# schematic.net
KiCad netlist of a schematic drawn in Altium Designer
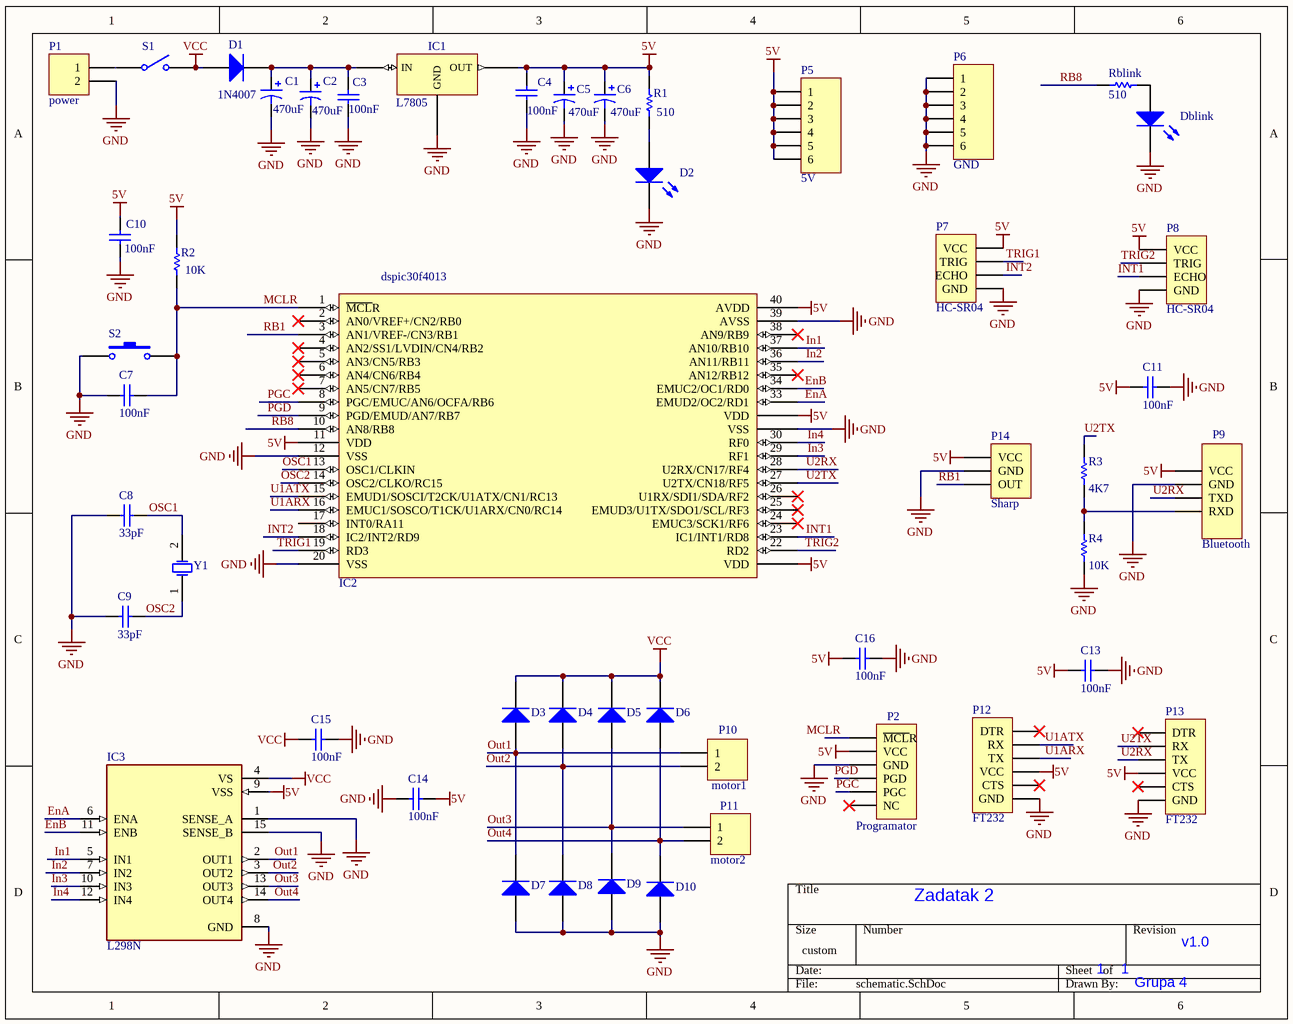
[diagram p0: schematic.SchDoc]

(export (version "E")
  (design (tool "Eeschema 10.0.6"))
  (components
    (comp (ref "C1")
      (value "470uF")
      (footprint "elektrolit")
      (description "Polarized Capacitor (Radial)")
      (fields (field (name "Comment") "Cap Pol1") (field (name "PUBLISHER") "Altium Limited"))
      (libsource (lib "Miscellaneous Devices") (part "Capacitor"))
    )
    (comp (ref "C2")
      (value "470uF")
      (footprint "elektrolit")
      (description "Polarized Capacitor (Radial)")
      (fields (field (name "Comment") "Cap Pol1") (field (name "PUBLISHER") "Altium Limited"))
      (libsource (lib "Miscellaneous Devices") (part "Capacitor"))
    )
    (comp (ref "C3")
      (value "100nF")
      (footprint "keramicki")
      (description "Capacitor")
      (fields (field (name "Comment") "Cap") (field (name "PUBLISHER") "Altium Limited"))
      (libsource (lib "Miscellaneous Devices") (part "Cap"))
    )
    (comp (ref "C4")
      (value "100nF")
      (footprint "keramicki")
      (description "Capacitor")
      (fields (field (name "Comment") "Cap") (field (name "PUBLISHER") "Altium Limited"))
      (libsource (lib "Miscellaneous Devices") (part "Cap"))
    )
    (comp (ref "C5")
      (value "470uF")
      (footprint "elektrolit")
      (description "Polarized Capacitor (Radial)")
      (fields (field (name "Comment") "Cap Pol1") (field (name "PUBLISHER") "Altium Limited"))
      (libsource (lib "Miscellaneous Devices") (part "Capacitor"))
    )
    (comp (ref "C6")
      (value "470uF")
      (footprint "elektrolit")
      (description "Polarized Capacitor (Radial)")
      (fields (field (name "Comment") "Cap Pol1") (field (name "PUBLISHER") "Altium Limited"))
      (libsource (lib "Miscellaneous Devices") (part "Capacitor"))
    )
    (comp (ref "C7")
      (value "100nF")
      (footprint "keramicki")
      (description "Capacitor")
      (fields (field (name "Comment") "Cap") (field (name "PUBLISHER") "Altium Limited"))
      (libsource (lib "Miscellaneous Devices") (part "Cap"))
    )
    (comp (ref "C8")
      (value "33pF")
      (footprint "keramicki")
      (description "Capacitor")
      (fields (field (name "Comment") "Cap") (field (name "PUBLISHER") "Altium Limited"))
      (libsource (lib "Miscellaneous Devices") (part "Cap"))
    )
    (comp (ref "C9")
      (value "33pF")
      (footprint "keramicki")
      (description "Capacitor")
      (fields (field (name "Comment") "Cap") (field (name "PUBLISHER") "Altium Limited"))
      (libsource (lib "Miscellaneous Devices") (part "Cap"))
    )
    (comp (ref "C10")
      (value "100nF")
      (footprint "keramicki")
      (description "Capacitor")
      (fields (field (name "Comment") "Cap") (field (name "PUBLISHER") "Altium Limited"))
      (libsource (lib "Miscellaneous Devices") (part "Cap"))
    )
    (comp (ref "C11")
      (value "100nF")
      (footprint "keramicki")
      (description "Capacitor")
      (fields (field (name "Comment") "Cap") (field (name "PUBLISHER") "Altium Limited"))
      (libsource (lib "Miscellaneous Devices") (part "Cap"))
    )
    (comp (ref "C13")
      (value "100nF")
      (footprint "keramicki")
      (description "Capacitor")
      (fields (field (name "Comment") "Cap") (field (name "PUBLISHER") "Altium Limited"))
      (libsource (lib "Miscellaneous Devices") (part "Cap"))
    )
    (comp (ref "C14")
      (value "100nF")
      (footprint "keramicki")
      (description "Capacitor")
      (fields (field (name "Comment") "Cap") (field (name "PUBLISHER") "Altium Limited"))
      (libsource (lib "Miscellaneous Devices") (part "Cap"))
    )
    (comp (ref "C15")
      (value "100nF")
      (footprint "keramicki")
      (description "Capacitor")
      (fields (field (name "Comment") "Cap") (field (name "PUBLISHER") "Altium Limited"))
      (libsource (lib "Miscellaneous Devices") (part "Cap"))
    )
    (comp (ref "C16")
      (value "100nF")
      (footprint "keramicki")
      (description "Capacitor")
      (fields (field (name "Comment") "Cap") (field (name "PUBLISHER") "Altium Limited"))
      (libsource (lib "Miscellaneous Devices") (part "Cap"))
    )
    (comp (ref "D1")
      (value "1N4007")
      (footprint "DIOD")
      (description "1 Amp General Purpose Rectifier")
      (fields (field (name "PUBLISHER") "Altium Limited"))
      (libsource (lib "Miscellaneous Devices") (part "Diode 1N4007"))
    )
    (comp (ref "D2")
      (value "LED0")
      (footprint "led")
      (description "Typical INFRARED GaAs LED")
      (fields (field (name "PUBLISHER") "Altium Limited"))
      (libsource (lib "Miscellaneous Devices") (part "LED0"))
    )
    (comp (ref "D3")
      (value "Diode 1N4007")
      (footprint "DIOD")
      (description "1 Amp General Purpose Rectifier")
      (fields (field (name "PUBLISHER") "Altium Limited"))
      (libsource (lib "Miscellaneous Devices") (part "Diode 1N4007"))
    )
    (comp (ref "D4")
      (value "Diode 1N4007")
      (footprint "DIOD")
      (description "1 Amp General Purpose Rectifier")
      (fields (field (name "PUBLISHER") "Altium Limited"))
      (libsource (lib "Miscellaneous Devices") (part "Diode 1N4007"))
    )
    (comp (ref "D5")
      (value "Diode 1N4007")
      (footprint "DIOD")
      (description "1 Amp General Purpose Rectifier")
      (fields (field (name "PUBLISHER") "Altium Limited"))
      (libsource (lib "Miscellaneous Devices") (part "Diode 1N4007"))
    )
    (comp (ref "D6")
      (value "Diode 1N4007")
      (footprint "DIOD")
      (description "1 Amp General Purpose Rectifier")
      (fields (field (name "PUBLISHER") "Altium Limited"))
      (libsource (lib "Miscellaneous Devices") (part "Diode 1N4007"))
    )
    (comp (ref "D7")
      (value "Diode 1N4007")
      (footprint "DIOD")
      (description "1 Amp General Purpose Rectifier")
      (fields (field (name "PUBLISHER") "Altium Limited"))
      (libsource (lib "Miscellaneous Devices") (part "Diode 1N4007"))
    )
    (comp (ref "D8")
      (value "Diode 1N4007")
      (footprint "DIOD")
      (description "1 Amp General Purpose Rectifier")
      (fields (field (name "PUBLISHER") "Altium Limited"))
      (libsource (lib "Miscellaneous Devices") (part "Diode 1N4007"))
    )
    (comp (ref "D9")
      (value "Diode 1N4007")
      (footprint "DIOD")
      (description "1 Amp General Purpose Rectifier")
      (fields (field (name "PUBLISHER") "Altium Limited"))
      (libsource (lib "Miscellaneous Devices") (part "Diode 1N4007"))
    )
    (comp (ref "D10")
      (value "Diode 1N4007")
      (footprint "DIOD")
      (description "1 Amp General Purpose Rectifier")
      (fields (field (name "PUBLISHER") "Altium Limited"))
      (libsource (lib "Miscellaneous Devices") (part "Diode 1N4007"))
    )
    (comp (ref "Dblink")
      (value "LED0")
      (footprint "led")
      (description "Typical INFRARED GaAs LED")
      (fields (field (name "PUBLISHER") "Altium Limited"))
      (libsource (lib "Miscellaneous Devices") (part "LED0"))
    )
    (comp (ref "IC1") (value "L7805") (footprint "stabilizator") (libsource (lib "Schlib1") (part "L7805")))
    (comp (ref "IC2")
      (value "dspic30f4013")
      (footprint "dspic")
      (libsource (lib "Schlib1") (part "dspic30f4013"))
    )
    (comp (ref "IC3")
      (value "L298N")
      (footprint "l298n:l298n")
      (description "Dual Full Bridge Motor Driver 15-Pin(15+Tab) MULTIWATT V Tube")
      (libsource (lib "drajver") (part "L298N"))
    )
    (comp (ref "P1")
      (value "power")
      (footprint "terminal2")
      (description "Header, 2-Pin")
      (fields (field (name "PUBLISHER") "Altium Limited"))
      (libsource (lib "") (part "Header 2_1"))
    )
    (comp (ref "P2")
      (value "Programator")
      (footprint "HDR1X5")
      (description "Header, 6-Pin")
      (fields (field (name "PUBLISHER") "Altium Limited"))
      (libsource (lib "") (part "Header 6_2"))
    )
    (comp (ref "P5")
      (value "5V")
      (footprint "HDR1X3")
      (description "Header, 6-Pin")
      (fields (field (name "PUBLISHER") "Altium Limited"))
      (libsource (lib "Miscellaneous Connectors") (part "Header 6"))
    )
    (comp (ref "P6")
      (value "GND")
      (footprint "HDR1X3")
      (description "Header, 6-Pin")
      (fields (field (name "PUBLISHER") "Altium Limited"))
      (libsource (lib "Miscellaneous Connectors") (part "Header 6"))
    )
    (comp (ref "P7")
      (value "HC-SR04")
      (footprint "HDR1X4")
      (description "Header, 4-Pin")
      (fields (field (name "PUBLISHER") "Altium Limited"))
      (libsource (lib "") (part "Header 4_1"))
    )
    (comp (ref "P8")
      (value "HC-SR04")
      (footprint "HDR1X4")
      (description "Header, 4-Pin")
      (fields (field (name "PUBLISHER") "Altium Limited"))
      (libsource (lib "Miscellaneous Connectors") (part "Header 4"))
    )
    (comp (ref "P9")
      (value "Bluetooth")
      (footprint "HDR1X4")
      (description "Header, 6-Pin")
      (fields (field (name "PUBLISHER") "Altium Limited"))
      (libsource (lib "") (part "Header 6_4"))
    )
    (comp (ref "P10")
      (value "motor1")
      (footprint "terminal2")
      (description "Header, 2-Pin")
      (fields (field (name "PUBLISHER") "Altium Limited"))
      (libsource (lib "Miscellaneous Connectors") (part "Header 2"))
    )
    (comp (ref "P11")
      (value "motor2")
      (footprint "terminal2")
      (description "Header, 2-Pin")
      (fields (field (name "PUBLISHER") "Altium Limited"))
      (libsource (lib "Miscellaneous Connectors") (part "Header 2"))
    )
    (comp (ref "P12")
      (value "FT232")
      (footprint "HDR1X6")
      (description "Header, 6-Pin")
      (fields (field (name "PUBLISHER") "Altium Limited"))
      (libsource (lib "") (part "Header 6_1"))
    )
    (comp (ref "P13")
      (value "FT232")
      (footprint "HDR1X6")
      (description "Header, 6-Pin")
      (fields (field (name "PUBLISHER") "Altium Limited"))
      (libsource (lib "") (part "Header 6_3"))
    )
    (comp (ref "P14")
      (value "Sharp")
      (footprint "HDR1X3")
      (description "Header, 3-Pin")
      (fields (field (name "PUBLISHER") "Altium Limited"))
      (libsource (lib "Miscellaneous Connectors") (part "Header 3"))
    )
    (comp (ref "R1")
      (value "510")
      (footprint "otp")
      (description "Resistor")
      (fields (field (name "Comment") "Res1") (field (name "PUBLISHER") "Altium Limited"))
      (libsource (lib "Miscellaneous Devices") (part "Res1"))
    )
    (comp (ref "R2")
      (value "10K")
      (footprint "otp")
      (description "Resistor")
      (fields (field (name "Comment") "Res1") (field (name "PUBLISHER") "Altium Limited"))
      (libsource (lib "Miscellaneous Devices") (part "Res1"))
    )
    (comp (ref "R3")
      (value "4K7")
      (footprint "otp")
      (description "Resistor")
      (fields (field (name "Comment") "Res1") (field (name "PUBLISHER") "Altium Limited"))
      (libsource (lib "Miscellaneous Devices") (part "Res1"))
    )
    (comp (ref "R4")
      (value "10K")
      (footprint "otp")
      (description "Resistor")
      (fields (field (name "Comment") "Res1") (field (name "PUBLISHER") "Altium Limited"))
      (libsource (lib "Miscellaneous Devices") (part "Res1"))
    )
    (comp (ref "Rblink")
      (value "510")
      (footprint "otp")
      (description "Resistor")
      (fields (field (name "Comment") "Res1") (field (name "PUBLISHER") "Altium Limited"))
      (libsource (lib "Miscellaneous Devices") (part "Res1"))
    )
    (comp (ref "S1")
      (value "SW-SPST")
      (footprint "Prekidac")
      (description "Single-Pole, Single-Throw Switch")
      (fields (field (name "PUBLISHER") "Altium Limited"))
      (libsource (lib "Miscellaneous Devices") (part "SW-SPST"))
    )
    (comp (ref "S2")
      (value "SW-PB")
      (footprint "taster")
      (description "Switch")
      (fields (field (name "PUBLISHER") "Altium Limited"))
      (libsource (lib "Miscellaneous Devices") (part "SW-PB"))
    )
    (comp (ref "Y1")
      (value "XTAL")
      (footprint "oscilator")
      (description "Crystal Oscillator")
      (fields (field (name "PUBLISHER") "Altium Limited"))
      (libsource (lib "Miscellaneous Devices") (part "XTAL"))
    )
  )
  (nets
    (net (code "1") (name "/EnA") (class "Default")
      (node (ref "IC2") (pin "33") (pinfunction "EMUD2/OC2/RD1_33") (pintype "bidirectional"))
      (node (ref "IC3") (pin "6") (pinfunction "ENA_6") (pintype "input"))
    )
    (net (code "2") (name "/EnB") (class "Default")
      (node (ref "IC2") (pin "34") (pinfunction "EMUC2/OC1/RD0_34") (pintype "bidirectional"))
      (node (ref "IC3") (pin "11") (pinfunction "ENB_11") (pintype "input"))
    )
    (net (code "3") (name "/INT1") (class "Default")
      (node (ref "IC2") (pin "23") (pinfunction "IC1/INT1/RD8_23") (pintype "bidirectional"))
      (node (ref "P8") (pin "3") (pinfunction "ECHO_3") (pintype "passive"))
    )
    (net (code "4") (name "/INT2") (class "Default")
      (node (ref "IC2") (pin "18") (pinfunction "IC2/INT2/RD9_18") (pintype "bidirectional"))
      (node (ref "P7") (pin "3") (pinfunction "ECHO_3") (pintype "passive"))
    )
    (net (code "5") (name "/In1") (class "Default")
      (node (ref "IC2") (pin "37") (pinfunction "AN10/RB10_37") (pintype "bidirectional"))
      (node (ref "IC3") (pin "5") (pinfunction "IN1_5") (pintype "input"))
    )
    (net (code "6") (name "/In2") (class "Default")
      (node (ref "IC2") (pin "36") (pinfunction "AN11/RB11_36") (pintype "bidirectional"))
      (node (ref "IC3") (pin "7") (pinfunction "IN2_7") (pintype "input"))
    )
    (net (code "7") (name "/In3") (class "Default")
      (node (ref "IC2") (pin "29") (pinfunction "RF1_29") (pintype "bidirectional"))
      (node (ref "IC3") (pin "10") (pinfunction "IN3_10") (pintype "input"))
    )
    (net (code "8") (name "/In4") (class "Default")
      (node (ref "IC2") (pin "30") (pinfunction "RF0_30") (pintype "bidirectional"))
      (node (ref "IC3") (pin "12") (pinfunction "IN4_12") (pintype "input"))
    )
    (net (code "9") (name "/MCLR") (class "Default")
      (node (ref "C7") (pin "2") (pinfunction "2_2") (pintype "passive"))
      (node (ref "IC2") (pin "1") (pinfunction "~{MCL}R_1") (pintype "bidirectional"))
      (node (ref "P2") (pin "1") (pinfunction "~{MCL}R_1") (pintype "passive"))
      (node (ref "R2") (pin "1") (pinfunction "1_1") (pintype "passive"))
      (node (ref "S2") (pin "2") (pinfunction "2_2") (pintype "passive"))
    )
    (net (code "10") (name "/OSC1") (class "Default")
      (node (ref "C8") (pin "1") (pinfunction "1_1") (pintype "passive"))
      (node (ref "IC2") (pin "13") (pinfunction "OSC1/CLKIN_13") (pintype "bidirectional"))
      (node (ref "Y1") (pin "2") (pinfunction "OSC2_2") (pintype "passive"))
    )
    (net (code "11") (name "/OSC2") (class "Default")
      (node (ref "C9") (pin "1") (pinfunction "1_1") (pintype "passive"))
      (node (ref "IC2") (pin "14") (pinfunction "OSC2/CLKO/RC15_14") (pintype "bidirectional"))
      (node (ref "Y1") (pin "1") (pinfunction "OSC1_1") (pintype "passive"))
    )
    (net (code "12") (name "/Out1") (class "Default")
      (node (ref "D3") (pin "1") (pinfunction "A_1") (pintype "passive"))
      (node (ref "D7") (pin "2") (pinfunction "K_2") (pintype "passive"))
      (node (ref "IC3") (pin "2") (pinfunction "OUT1_2") (pintype "output"))
      (node (ref "P10") (pin "1") (pinfunction "1_1") (pintype "passive"))
    )
    (net (code "13") (name "/Out2") (class "Default")
      (node (ref "D4") (pin "1") (pinfunction "A_1") (pintype "passive"))
      (node (ref "D8") (pin "2") (pinfunction "K_2") (pintype "passive"))
      (node (ref "IC3") (pin "3") (pinfunction "OUT2_3") (pintype "output"))
      (node (ref "P10") (pin "2") (pinfunction "2_2") (pintype "passive"))
    )
    (net (code "14") (name "/Out3") (class "Default")
      (node (ref "D5") (pin "1") (pinfunction "A_1") (pintype "passive"))
      (node (ref "D9") (pin "2") (pinfunction "K_2") (pintype "passive"))
      (node (ref "IC3") (pin "13") (pinfunction "OUT3_13") (pintype "output"))
      (node (ref "P11") (pin "1") (pinfunction "1_1") (pintype "passive"))
    )
    (net (code "15") (name "/Out4") (class "Default")
      (node (ref "D10") (pin "2") (pinfunction "K_2") (pintype "passive"))
      (node (ref "D6") (pin "1") (pinfunction "A_1") (pintype "passive"))
      (node (ref "IC3") (pin "14") (pinfunction "OUT4_14") (pintype "output"))
      (node (ref "P11") (pin "2") (pinfunction "2_2") (pintype "passive"))
    )
    (net (code "16") (name "/PGC") (class "Default")
      (node (ref "IC2") (pin "8") (pinfunction "PGC/EMUC/AN6/OCFA/RB6_8") (pintype "bidirectional"))
      (node (ref "P2") (pin "5") (pinfunction "PGC_5") (pintype "passive"))
    )
    (net (code "17") (name "/PGD") (class "Default")
      (node (ref "IC2") (pin "9") (pinfunction "PGD/EMUD/AN7/RB7_9") (pintype "bidirectional"))
      (node (ref "P2") (pin "4") (pinfunction "PGD_4") (pintype "passive"))
    )
    (net (code "18") (name "/RB1") (class "Default")
      (node (ref "IC2") (pin "3") (pinfunction "AN1/VREF-/CN3/RB1_3") (pintype "bidirectional"))
      (node (ref "P14") (pin "3") (pinfunction "OUT_3") (pintype "passive"))
    )
    (net (code "19") (name "/RB8") (class "Default")
      (node (ref "IC2") (pin "10") (pinfunction "AN8/RB8_10") (pintype "bidirectional"))
      (node (ref "Rblink") (pin "2") (pinfunction "2_2") (pintype "passive"))
    )
    (net (code "20") (name "/TRIG1") (class "Default")
      (node (ref "IC2") (pin "19") (pinfunction "RD3_19") (pintype "bidirectional"))
      (node (ref "P7") (pin "2") (pinfunction "TRIG_2") (pintype "passive"))
    )
    (net (code "21") (name "/TRIG2") (class "Default")
      (node (ref "IC2") (pin "22") (pinfunction "RD2_22") (pintype "bidirectional"))
      (node (ref "P8") (pin "2") (pinfunction "TRIG_2") (pintype "passive"))
    )
    (net (code "22") (name "/U1ARX") (class "Default")
      (node (ref "IC2") (pin "16") (pinfunction "EMUC1/SOSCO/T1CK/U1ARX/CN0/RC14_16") (pintype "bidirectional"))
      (node (ref "P12") (pin "3") (pinfunction "TX_3") (pintype "passive"))
    )
    (net (code "23") (name "/U1ATX") (class "Default")
      (node (ref "IC2") (pin "15") (pinfunction "EMUD1/SOSCI/T2CK/U1ATX/CN1/RC13_15") (pintype "bidirectional"))
      (node (ref "P12") (pin "2") (pinfunction "RX_2") (pintype "passive"))
    )
    (net (code "24") (name "/U2RX") (class "Default")
      (node (ref "IC2") (pin "28") (pinfunction "U2RX/CN17/RF4_28") (pintype "bidirectional"))
      (node (ref "P13") (pin "3") (pinfunction "TX_3") (pintype "passive"))
      (node (ref "P9") (pin "3") (pinfunction "TXD_3") (pintype "passive"))
    )
    (net (code "25") (name "/U2TX") (class "Default")
      (node (ref "IC2") (pin "27") (pinfunction "U2TX/CN18/RF5_27") (pintype "bidirectional"))
      (node (ref "P13") (pin "2") (pinfunction "RX_2") (pintype "passive"))
      (node (ref "R3") (pin "2") (pinfunction "2_2") (pintype "passive"))
    )
    (net (code "26") (name "5V") (class "Default")
      (node (ref "C10") (pin "2") (pinfunction "2_2") (pintype "passive"))
      (node (ref "C11") (pin "2") (pinfunction "2_2") (pintype "passive"))
      (node (ref "C13") (pin "2") (pinfunction "2_2") (pintype "passive"))
      (node (ref "C14") (pin "2") (pinfunction "2_2") (pintype "passive"))
      (node (ref "C16") (pin "2") (pinfunction "2_2") (pintype "passive"))
      (node (ref "C4") (pin "2") (pinfunction "2_2") (pintype "passive"))
      (node (ref "C5") (pin "1") (pinfunction "1_1") (pintype "passive"))
      (node (ref "C6") (pin "1") (pinfunction "1_1") (pintype "passive"))
      (node (ref "IC1") (pin "3") (pinfunction "OUT_3") (pintype "output"))
      (node (ref "IC2") (pin "11") (pinfunction "VDD_11") (pintype "passive"))
      (node (ref "IC2") (pin "21") (pinfunction "VDD_21") (pintype "passive"))
      (node (ref "IC2") (pin "32") (pinfunction "VDD_32") (pintype "passive"))
      (node (ref "IC2") (pin "40") (pinfunction "AVDD_40") (pintype "passive"))
      (node (ref "IC3") (pin "9") (pinfunction "VSS_9") (pintype "input"))
      (node (ref "P12") (pin "4") (pinfunction "VCC_4") (pintype "passive"))
      (node (ref "P13") (pin "4") (pinfunction "VCC_4") (pintype "passive"))
      (node (ref "P14") (pin "1") (pinfunction "VCC_1") (pintype "passive"))
      (node (ref "P2") (pin "2") (pinfunction "VCC_2") (pintype "passive"))
      (node (ref "P5") (pin "1") (pinfunction "1_1") (pintype "passive"))
      (node (ref "P5") (pin "2") (pinfunction "2_2") (pintype "passive"))
      (node (ref "P5") (pin "3") (pinfunction "3_3") (pintype "passive"))
      (node (ref "P5") (pin "4") (pinfunction "4_4") (pintype "passive"))
      (node (ref "P5") (pin "5") (pinfunction "5_5") (pintype "passive"))
      (node (ref "P5") (pin "6") (pinfunction "6_6") (pintype "passive"))
      (node (ref "P7") (pin "1") (pinfunction "VCC_1") (pintype "passive"))
      (node (ref "P8") (pin "1") (pinfunction "VCC_1") (pintype "passive"))
      (node (ref "P9") (pin "1") (pinfunction "VCC_1") (pintype "passive"))
      (node (ref "R1") (pin "2") (pinfunction "2_2") (pintype "passive"))
      (node (ref "R2") (pin "2") (pinfunction "2_2") (pintype "passive"))
    )
    (net (code "27") (name "GND") (class "Default")
      (node (ref "C1") (pin "2") (pinfunction "2_2") (pintype "passive"))
      (node (ref "C10") (pin "1") (pinfunction "1_1") (pintype "passive"))
      (node (ref "C11") (pin "1") (pinfunction "1_1") (pintype "passive"))
      (node (ref "C13") (pin "1") (pinfunction "1_1") (pintype "passive"))
      (node (ref "C14") (pin "1") (pinfunction "1_1") (pintype "passive"))
      (node (ref "C15") (pin "1") (pinfunction "1_1") (pintype "passive"))
      (node (ref "C16") (pin "1") (pinfunction "1_1") (pintype "passive"))
      (node (ref "C2") (pin "2") (pinfunction "2_2") (pintype "passive"))
      (node (ref "C3") (pin "1") (pinfunction "1_1") (pintype "passive"))
      (node (ref "C4") (pin "1") (pinfunction "1_1") (pintype "passive"))
      (node (ref "C5") (pin "2") (pinfunction "2_2") (pintype "passive"))
      (node (ref "C6") (pin "2") (pinfunction "2_2") (pintype "passive"))
      (node (ref "C7") (pin "1") (pinfunction "1_1") (pintype "passive"))
      (node (ref "C8") (pin "2") (pinfunction "2_2") (pintype "passive"))
      (node (ref "C9") (pin "2") (pinfunction "2_2") (pintype "passive"))
      (node (ref "D10") (pin "1") (pinfunction "A_1") (pintype "passive"))
      (node (ref "D2") (pin "2") (pinfunction "K_2") (pintype "passive"))
      (node (ref "D7") (pin "1") (pinfunction "A_1") (pintype "passive"))
      (node (ref "D8") (pin "1") (pinfunction "A_1") (pintype "passive"))
      (node (ref "D9") (pin "1") (pinfunction "A_1") (pintype "passive"))
      (node (ref "Dblink") (pin "2") (pinfunction "K_2") (pintype "passive"))
      (node (ref "IC1") (pin "2") (pinfunction "GND_2") (pintype "passive"))
      (node (ref "IC2") (pin "12") (pinfunction "VSS_12") (pintype "passive"))
      (node (ref "IC2") (pin "20") (pinfunction "VSS_20") (pintype "passive"))
      (node (ref "IC2") (pin "31") (pinfunction "VSS_31") (pintype "passive"))
      (node (ref "IC2") (pin "39") (pinfunction "AVSS_39") (pintype "passive"))
      (node (ref "IC3") (pin "1") (pinfunction "SENSE_A_1") (pintype "passive"))
      (node (ref "IC3") (pin "15") (pinfunction "SENSE_B_15") (pintype "passive"))
      (node (ref "IC3") (pin "8") (pinfunction "GND_8") (pintype "passive"))
      (node (ref "P1") (pin "2") (pinfunction "2_2") (pintype "passive"))
      (node (ref "P12") (pin "6") (pinfunction "GND_6") (pintype "passive"))
      (node (ref "P13") (pin "6") (pinfunction "GND_6") (pintype "passive"))
      (node (ref "P14") (pin "2") (pinfunction "GND_2") (pintype "passive"))
      (node (ref "P2") (pin "3") (pinfunction "GND_3") (pintype "passive"))
      (node (ref "P6") (pin "1") (pinfunction "1_1") (pintype "passive"))
      (node (ref "P6") (pin "2") (pinfunction "2_2") (pintype "passive"))
      (node (ref "P6") (pin "3") (pinfunction "3_3") (pintype "passive"))
      (node (ref "P6") (pin "4") (pinfunction "4_4") (pintype "passive"))
      (node (ref "P6") (pin "5") (pinfunction "5_5") (pintype "passive"))
      (node (ref "P6") (pin "6") (pinfunction "6_6") (pintype "passive"))
      (node (ref "P7") (pin "4") (pinfunction "GND_4") (pintype "passive"))
      (node (ref "P8") (pin "4") (pinfunction "GND_4") (pintype "passive"))
      (node (ref "P9") (pin "2") (pinfunction "GND_2") (pintype "passive"))
      (node (ref "R4") (pin "1") (pinfunction "1_1") (pintype "passive"))
      (node (ref "S2") (pin "1") (pinfunction "1_1") (pintype "passive"))
    )
    (net (code "28") (name "Net-(D1-K)") (class "Default")
      (node (ref "C1") (pin "1") (pinfunction "1_1") (pintype "passive"))
      (node (ref "C2") (pin "1") (pinfunction "1_1") (pintype "passive"))
      (node (ref "C3") (pin "2") (pinfunction "2_2") (pintype "passive"))
      (node (ref "D1") (pin "2") (pinfunction "K_2") (pintype "passive"))
      (node (ref "IC1") (pin "1") (pinfunction "IN_1") (pintype "bidirectional"))
    )
    (net (code "29") (name "Net-(D2-A)") (class "Default")
      (node (ref "D2") (pin "1") (pinfunction "A_1") (pintype "passive"))
      (node (ref "R1") (pin "1") (pinfunction "1_1") (pintype "passive"))
    )
    (net (code "30") (name "Net-(Dblink-A)") (class "Default")
      (node (ref "Dblink") (pin "1") (pinfunction "A_1") (pintype "passive"))
      (node (ref "Rblink") (pin "1") (pinfunction "1_1") (pintype "passive"))
    )
    (net (code "31") (name "Net-(P9-RXD)") (class "Default")
      (node (ref "P9") (pin "4") (pinfunction "RXD_4") (pintype "passive"))
      (node (ref "R3") (pin "1") (pinfunction "1_1") (pintype "passive"))
      (node (ref "R4") (pin "2") (pinfunction "2_2") (pintype "passive"))
    )
    (net (code "32") (name "Net-(S1-COMMON)") (class "Default")
      (node (ref "P1") (pin "1") (pinfunction "1_1") (pintype "passive"))
      (node (ref "S1") (pin "1") (pinfunction "COMMON_1") (pintype "passive"))
    )
    (net (code "33") (name "VCC") (class "Default")
      (node (ref "C15") (pin "2") (pinfunction "2_2") (pintype "passive"))
      (node (ref "D1") (pin "1") (pinfunction "A_1") (pintype "passive"))
      (node (ref "D3") (pin "2") (pinfunction "K_2") (pintype "passive"))
      (node (ref "D4") (pin "2") (pinfunction "K_2") (pintype "passive"))
      (node (ref "D5") (pin "2") (pinfunction "K_2") (pintype "passive"))
      (node (ref "D6") (pin "2") (pinfunction "K_2") (pintype "passive"))
      (node (ref "IC3") (pin "4") (pinfunction "VS_4") (pintype "power_in"))
      (node (ref "S1") (pin "2") (pinfunction "NO_2") (pintype "passive"))
    )
    (net (code "34") (name "unconnected-(IC2-AN0{slash}VREF+{slash}CN2{slash}RB0-Pad2)") (class "Default")
      (node (ref "IC2") (pin "2") (pinfunction "AN0/VREF+/CN2/RB0_2") (pintype "bidirectional+no_connect"))
    )
    (net (code "35") (name "unconnected-(IC2-AN2{slash}SS1{slash}LVDIN{slash}CN4{slash}RB2-Pad4)") (class "Default")
      (node (ref "IC2") (pin "4") (pinfunction "AN2/SS1/LVDIN/CN4/RB2_4") (pintype "bidirectional+no_connect"))
    )
    (net (code "36") (name "unconnected-(IC2-AN3{slash}CN5{slash}RB3-Pad5)") (class "Default")
      (node (ref "IC2") (pin "5") (pinfunction "AN3/CN5/RB3_5") (pintype "bidirectional+no_connect"))
    )
    (net (code "37") (name "unconnected-(IC2-AN4{slash}CN6{slash}RB4-Pad6)") (class "Default")
      (node (ref "IC2") (pin "6") (pinfunction "AN4/CN6/RB4_6") (pintype "bidirectional+no_connect"))
    )
    (net (code "38") (name "unconnected-(IC2-AN5{slash}CN7{slash}RB5-Pad7)") (class "Default")
      (node (ref "IC2") (pin "7") (pinfunction "AN5/CN7/RB5_7") (pintype "bidirectional+no_connect"))
    )
    (net (code "39") (name "unconnected-(IC2-AN9{slash}RB9-Pad38)") (class "Default")
      (node (ref "IC2") (pin "38") (pinfunction "AN9/RB9_38") (pintype "bidirectional+no_connect"))
    )
    (net (code "40") (name "unconnected-(IC2-AN12{slash}RB12-Pad35)") (class "Default")
      (node (ref "IC2") (pin "35") (pinfunction "AN12/RB12_35") (pintype "bidirectional+no_connect"))
    )
    (net (code "41") (name "unconnected-(IC2-EMUC3{slash}SCK1{slash}RF6-Pad24)") (class "Default")
      (node (ref "IC2") (pin "24") (pinfunction "EMUC3/SCK1/RF6_24") (pintype "bidirectional+no_connect"))
    )
    (net (code "42") (name "unconnected-(IC2-EMUD3{slash}U1TX{slash}SDO1{slash}SCL{slash}RF3-Pad25)") (class "Default")
      (node (ref "IC2") (pin "25") (pinfunction "EMUD3/U1TX/SDO1/SCL/RF3_25") (pintype "bidirectional+no_connect"))
    )
    (net (code "43") (name "unconnected-(IC2-INT0{slash}RA11-Pad17)") (class "Default")
      (node (ref "IC2") (pin "17") (pinfunction "INT0/RA11_17") (pintype "bidirectional"))
    )
    (net (code "44") (name "unconnected-(IC2-U1RX{slash}SDI1{slash}SDA{slash}RF2-Pad26)") (class "Default")
      (node (ref "IC2") (pin "26") (pinfunction "U1RX/SDI1/SDA/RF2_26") (pintype "bidirectional+no_connect"))
    )
    (net (code "45") (name "unconnected-(P2-NC-Pad6)") (class "Default")
      (node (ref "P2") (pin "6") (pinfunction "NC_6") (pintype "passive+no_connect"))
    )
    (net (code "46") (name "unconnected-(P12-CTS-Pad5)") (class "Default")
      (node (ref "P12") (pin "5") (pinfunction "CTS_5") (pintype "passive+no_connect"))
    )
    (net (code "47") (name "unconnected-(P12-DTR-Pad1)") (class "Default")
      (node (ref "P12") (pin "1") (pinfunction "DTR_1") (pintype "passive+no_connect"))
    )
    (net (code "48") (name "unconnected-(P13-CTS-Pad5)") (class "Default")
      (node (ref "P13") (pin "5") (pinfunction "CTS_5") (pintype "passive+no_connect"))
    )
    (net (code "49") (name "unconnected-(P13-DTR-Pad1)") (class "Default")
      (node (ref "P13") (pin "1") (pinfunction "DTR_1") (pintype "passive+no_connect"))
    )
  )
)
